# FPGA_ADC1.net
KiCad netlist of a schematic drawn in Altium Designer
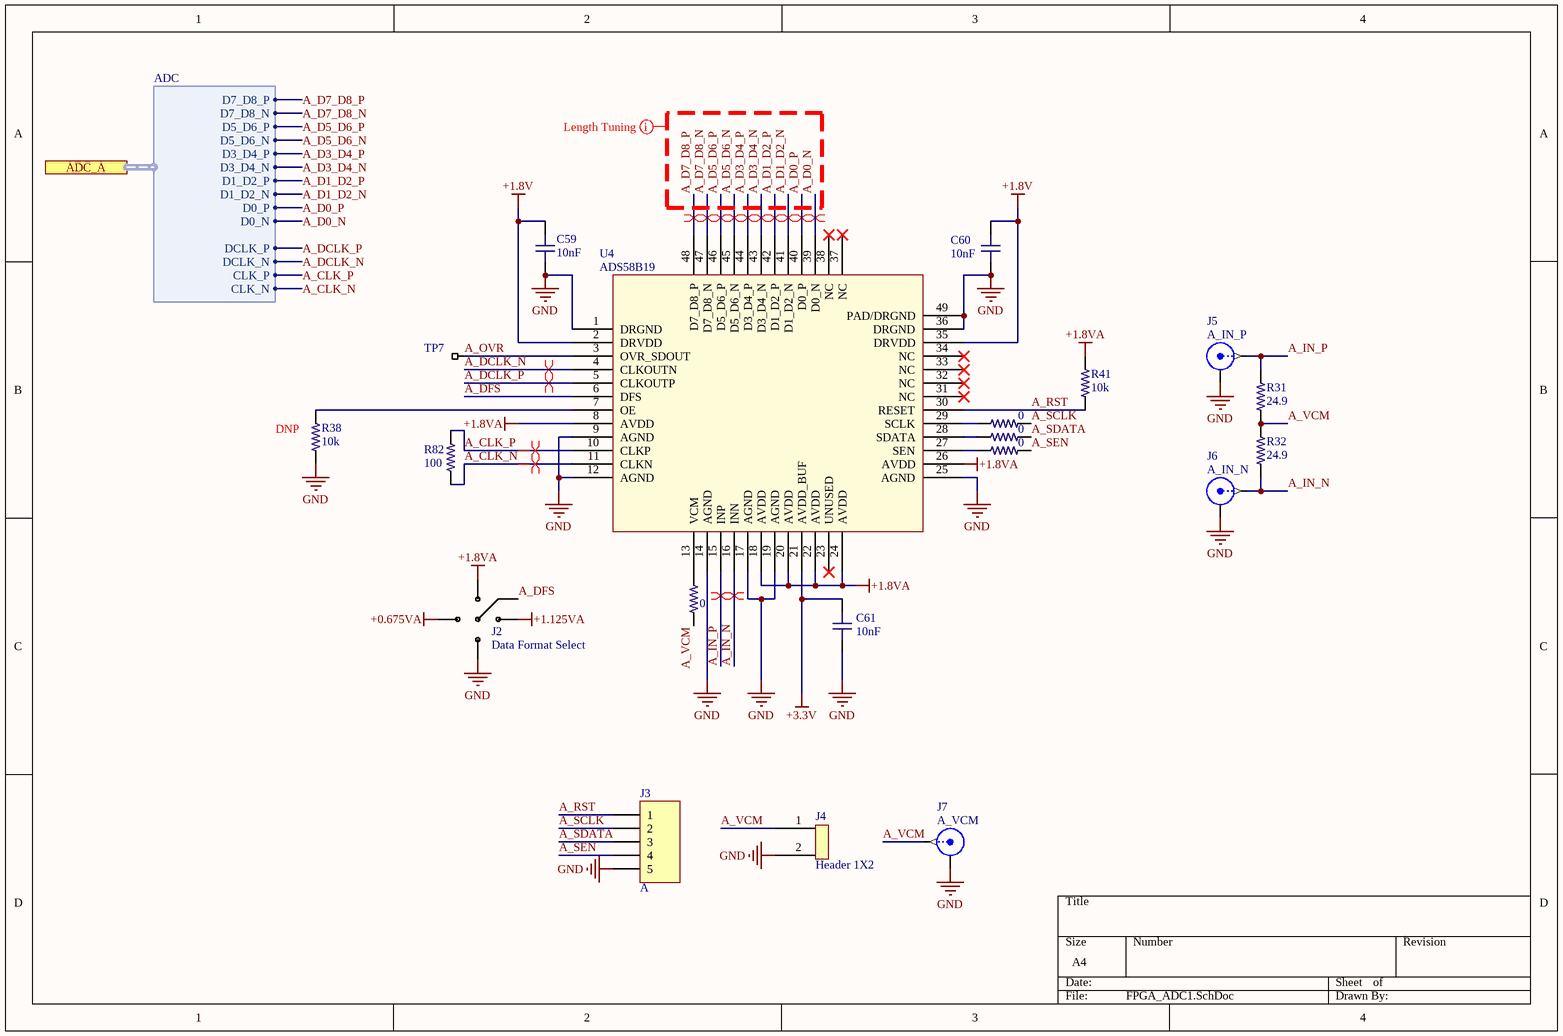
[diagram p0: FPGA_ADC1.SchDoc]

(export (version "E")
  (design (tool "Eeschema 10.0.6"))
  (components
    (comp (ref "C59")
      (value "10nF")
      (footprint "C0603-HIGH-DENSITY")
      (description "CAP CER 10000PF 50V X7R 0603")
      (fields (field (name "Comment") "C0603 10nF 50V X7R"))
      (libsource (lib "Capacitors") (part "C0603 10nF 50V X7R"))
    )
    (comp (ref "C60")
      (value "10nF")
      (footprint "C0603-HIGH-DENSITY")
      (description "CAP CER 10000PF 50V X7R 0603")
      (fields (field (name "Comment") "C0603 10nF 50V X7R"))
      (libsource (lib "Capacitors") (part "C0603 10nF 50V X7R"))
    )
    (comp (ref "C61")
      (value "10nF")
      (footprint "C0603-HIGH-DENSITY")
      (description "CAP CER 10000PF 50V X7R 0603")
      (fields (field (name "Comment") "C0603 10nF 50V X7R"))
      (libsource (lib "Capacitors") (part "C0603 10nF 50V X7R"))
    )
    (comp (ref "J2")
      (value "Data Format Select")
      (footprint "4P Jumper")
      (description "0603 4 Way Solder Jumper")
      (libsource (lib "Switches") (part "4P Jumper"))
    )
    (comp (ref "J3")
      (value "A")
      (footprint "HDR1X5")
      (description "Header, 5-Pin")
      (fields (field (name "PUBLISHER") "Altium Limited"))
      (libsource (lib "Miscellaneous Connectors") (part "Header 5"))
    )
    (comp (ref "J4")
      (value "Header 1X2")
      (footprint "Header 1x2 TH Pitch 2.54mm")
      (libsource (lib "Connectors") (part "Header 1X2"))
    )
    (comp (ref "J5")
      (value "A_IN_P")
      (footprint "SMA Edge Launch (Horizontal)")
      (description "SMA Connector")
      (libsource (lib "Connectors") (part "SMA"))
    )
    (comp (ref "J6")
      (value "A_IN_N")
      (footprint "SMA Edge Launch (Horizontal)")
      (description "SMA Connector")
      (libsource (lib "Connectors") (part "SMA"))
    )
    (comp (ref "J7")
      (value "A_VCM")
      (footprint "SMA_CONN")
      (description "SMA Connector")
      (libsource (lib "") (part "SMA_1"))
    )
    (comp (ref "R31")
      (value "24.9")
      (footprint "R0603-HIGH-DENSITY")
      (description "Chip Resistor, 0603, 24.9 ohms, 0.1W")
      (fields (field (name "Comment") "RC0603FR-0724R9L"))
      (libsource (lib "Resistors") (part "R0603 24.9R 1%"))
    )
    (comp (ref "R32")
      (value "24.9")
      (footprint "R0603-HIGH-DENSITY")
      (description "Chip Resistor, 0603, 24.9 ohms, 0.1W")
      (fields (field (name "Comment") "RC0603FR-0724R9L"))
      (libsource (lib "Resistors") (part "R0603 24.9R 1%"))
    )
    (comp (ref "R36")
      (value "0")
      (footprint "R0603-IPC")
      (description "RES SMD 0 OHM JUMPER 1/10W 0603")
      (fields (field (name "Comment") "R0603 0"))
      (libsource (lib "Resistors") (part "R0603 0"))
    )
    (comp (ref "R37")
      (value "0")
      (footprint "R0603-IPC")
      (description "RES SMD 0 OHM JUMPER 1/10W 0603")
      (fields (field (name "Comment") "R0603 0"))
      (libsource (lib "Resistors") (part "R0603 0"))
    )
    (comp (ref "R38")
      (value "10k")
      (footprint "R0603-IPC-10K")
      (description "RES SMD 10K OHM 1% 1/10W 0603")
      (fields (field (name "Comment") "R0603 10K 1%"))
      (libsource (lib "Resistors") (part "R0603 10K 1%"))
    )
    (comp (ref "R39")
      (value "0")
      (footprint "R0603-IPC")
      (description "RES SMD 0 OHM JUMPER 1/10W 0603")
      (fields (field (name "Comment") "R0603 0"))
      (libsource (lib "Resistors") (part "R0603 0"))
    )
    (comp (ref "R40")
      (value "0")
      (footprint "R0603-IPC")
      (description "RES SMD 0 OHM JUMPER 1/10W 0603")
      (fields (field (name "Comment") "R0603 0"))
      (libsource (lib "Resistors") (part "R0603 0"))
    )
    (comp (ref "R41")
      (value "10k")
      (footprint "R0603-IPC-10K")
      (description "RES SMD 10K OHM 1% 1/10W 0603")
      (fields (field (name "Comment") "R0603 10K 1%"))
      (libsource (lib "Resistors") (part "R0603 10K 1%"))
    )
    (comp (ref "R82")
      (value "100")
      (footprint "R0402-HIGH-DENSITY")
      (description "Chip Resistor, 0402, 100 ohms, 1%, 1/16 W")
      (fields (field (name "Comment") "R0402 100R 1%"))
      (libsource (lib "Resistors") (part "R0402 100R 1%"))
    )
    (comp (ref "TP7")
      (value "Testpoint_SMT")
      (footprint "TESTPOINT_SMT")
      (description "SMT Test Point")
      (libsource (lib "Virtual Parts") (part "Testpoint_SMT"))
    )
    (comp (ref "U4")
      (value "ADS58B19")
      (footprint "VQFN48")
      (description "Single ADC Pipelined 250Msps 9-bit Parallel/LVDS 48-Pin VQFN")
      (libsource (lib "Integrated Circuits") (part "ADS58B19"))
    )
  )
  (nets
    (net (code "2") (name "+0.675VA") (class "Default")
      (node (ref "J2") (pin "4") (pinfunction "4_4") (pintype "passive"))
    )
    (net (code "3") (name "+1.8V") (class "Default")
      (node (ref "C59") (pin "1") (pintype "passive"))
      (node (ref "C60") (pin "1") (pintype "passive"))
      (node (ref "U4") (pin "2") (pinfunction "DRVDD_2") (pintype "passive"))
      (node (ref "U4") (pin "35") (pinfunction "DRVDD_35") (pintype "passive"))
    )
    (net (code "4") (name "+1.8VA") (class "Default")
      (node (ref "J2") (pin "1") (pinfunction "1_1") (pintype "passive"))
      (node (ref "R41") (pin "2") (pintype "passive"))
      (node (ref "U4") (pin "18") (pinfunction "AVDD_18") (pintype "passive"))
      (node (ref "U4") (pin "20") (pinfunction "AVDD_20") (pintype "passive"))
      (node (ref "U4") (pin "22") (pinfunction "AVDD_22") (pintype "passive"))
      (node (ref "U4") (pin "24") (pinfunction "AVDD_24") (pintype "passive"))
      (node (ref "U4") (pin "26") (pinfunction "AVDD_26") (pintype "passive"))
      (node (ref "U4") (pin "8") (pinfunction "AVDD_8") (pintype "passive"))
    )
    (net (code "5") (name "+1.125VA") (class "Default")
      (node (ref "J2") (pin "2") (pinfunction "2_2") (pintype "passive"))
    )
    (net (code "6") (name "+3.3V") (class "Default")
      (node (ref "C61") (pin "1") (pintype "passive"))
      (node (ref "U4") (pin "21") (pinfunction "AVDD_BUF_21") (pintype "passive"))
    )
    (net (code "7") (name "/A_CLK_N") (class "Default")
      (node (ref "R82") (pin "1") (pintype "passive"))
      (node (ref "U4") (pin "11") (pinfunction "CLKN_11") (pintype "passive"))
    )
    (net (code "8") (name "/A_CLK_P") (class "Default")
      (node (ref "R82") (pin "2") (pintype "passive"))
      (node (ref "U4") (pin "10") (pinfunction "CLKP_10") (pintype "passive"))
    )
    (net (code "9") (name "/A_D0_N") (class "Default")
      (node (ref "U4") (pin "39") (pinfunction "D0_N_39") (pintype "passive"))
    )
    (net (code "10") (name "/A_D0_P") (class "Default")
      (node (ref "U4") (pin "40") (pinfunction "D0_P_40") (pintype "passive"))
    )
    (net (code "11") (name "/A_D1_D2_N") (class "Default")
      (node (ref "U4") (pin "41") (pinfunction "D1_D2_N_41") (pintype "passive"))
    )
    (net (code "12") (name "/A_D1_D2_P") (class "Default")
      (node (ref "U4") (pin "42") (pinfunction "D1_D2_P_42") (pintype "passive"))
    )
    (net (code "13") (name "/A_D3_D4_N") (class "Default")
      (node (ref "U4") (pin "43") (pinfunction "D3_D4_N_43") (pintype "passive"))
    )
    (net (code "14") (name "/A_D3_D4_P") (class "Default")
      (node (ref "U4") (pin "44") (pinfunction "D3_D4_P_44") (pintype "passive"))
    )
    (net (code "15") (name "/A_D5_D6_N") (class "Default")
      (node (ref "U4") (pin "45") (pinfunction "D5_D6_N_45") (pintype "passive"))
    )
    (net (code "16") (name "/A_D5_D6_P") (class "Default")
      (node (ref "U4") (pin "46") (pinfunction "D5_D6_P_46") (pintype "passive"))
    )
    (net (code "17") (name "/A_D7_D8_N") (class "Default")
      (node (ref "U4") (pin "47") (pinfunction "D7_D8_N_47") (pintype "passive"))
    )
    (net (code "18") (name "/A_D7_D8_P") (class "Default")
      (node (ref "U4") (pin "48") (pinfunction "D7_D8_P_48") (pintype "passive"))
    )
    (net (code "19") (name "/A_DCLK_N") (class "Default")
      (node (ref "U4") (pin "4") (pinfunction "CLKOUTN_4") (pintype "passive"))
    )
    (net (code "20") (name "/A_DCLK_P") (class "Default")
      (node (ref "U4") (pin "5") (pinfunction "CLKOUTP_5") (pintype "passive"))
    )
    (net (code "21") (name "/A_DFS") (class "Default")
      (node (ref "J2") (pin "5") (pinfunction "5_5") (pintype "passive"))
      (node (ref "U4") (pin "6") (pinfunction "DFS_6") (pintype "passive"))
    )
    (net (code "22") (name "/A_IN_N") (class "Default")
      (node (ref "J6") (pin "1") (pinfunction "X_1") (pintype "output"))
      (node (ref "R32") (pin "1") (pintype "passive"))
      (node (ref "U4") (pin "16") (pinfunction "INN_16") (pintype "passive"))
    )
    (net (code "23") (name "/A_IN_P") (class "Default")
      (node (ref "J5") (pin "1") (pinfunction "X_1") (pintype "output"))
      (node (ref "R31") (pin "2") (pintype "passive"))
      (node (ref "U4") (pin "15") (pinfunction "INP_15") (pintype "passive"))
    )
    (net (code "24") (name "/A_OVR") (class "Default")
      (node (ref "TP7") (pin "1") (pinfunction "1_1") (pintype "passive"))
      (node (ref "U4") (pin "3") (pinfunction "OVR_SDOUT_3") (pintype "passive"))
    )
    (net (code "25") (name "/A_RST") (class "Default")
      (node (ref "J3") (pin "1") (pinfunction "1_1") (pintype "passive"))
      (node (ref "R41") (pin "1") (pintype "passive"))
      (node (ref "U4") (pin "30") (pinfunction "RESET_30") (pintype "passive"))
    )
    (net (code "26") (name "/A_SCLK") (class "Default")
      (node (ref "J3") (pin "2") (pinfunction "2_2") (pintype "passive"))
      (node (ref "R36") (pin "2") (pintype "passive"))
    )
    (net (code "27") (name "/A_SDATA") (class "Default")
      (node (ref "J3") (pin "3") (pinfunction "3_3") (pintype "passive"))
      (node (ref "R37") (pin "2") (pintype "passive"))
    )
    (net (code "28") (name "/A_SEN") (class "Default")
      (node (ref "J3") (pin "4") (pinfunction "4_4") (pintype "passive"))
      (node (ref "R39") (pin "2") (pintype "passive"))
    )
    (net (code "29") (name "/A_VCM") (class "Default")
      (node (ref "J4") (pin "1") (pintype "passive"))
      (node (ref "J7") (pin "C") (pinfunction "X_C") (pintype "output"))
      (node (ref "R31") (pin "1") (pintype "passive"))
      (node (ref "R32") (pin "2") (pintype "passive"))
      (node (ref "R40") (pin "2") (pintype "passive"))
    )
    (net (code "31") (name "GND") (class "Default")
      (node (ref "C59") (pin "2") (pintype "passive"))
      (node (ref "C60") (pin "2") (pintype "passive"))
      (node (ref "C61") (pin "2") (pintype "passive"))
      (node (ref "J2") (pin "3") (pinfunction "3_3") (pintype "passive"))
      (node (ref "J3") (pin "5") (pinfunction "5_5") (pintype "passive"))
      (node (ref "J4") (pin "2") (pintype "passive"))
      (node (ref "J5") (pin "2") (pinfunction "Y_2") (pintype "power_in"))
      (node (ref "J6") (pin "2") (pinfunction "Y_2") (pintype "power_in"))
      (node (ref "J7") (pin "G") (pinfunction "Y_G") (pintype "power_in"))
      (node (ref "R38") (pin "1") (pintype "passive"))
      (node (ref "U4") (pin "1") (pinfunction "DRGND_1") (pintype "passive"))
      (node (ref "U4") (pin "12") (pinfunction "AGND_12") (pintype "passive"))
      (node (ref "U4") (pin "14") (pinfunction "AGND_14") (pintype "passive"))
      (node (ref "U4") (pin "17") (pinfunction "AGND_17") (pintype "passive"))
      (node (ref "U4") (pin "19") (pinfunction "AGND_19") (pintype "passive"))
      (node (ref "U4") (pin "25") (pinfunction "AGND_25") (pintype "passive"))
      (node (ref "U4") (pin "36") (pinfunction "DRGND_36") (pintype "passive"))
      (node (ref "U4") (pin "49") (pinfunction "PAD/DRGND_49") (pintype "passive"))
      (node (ref "U4") (pin "9") (pinfunction "AGND_9") (pintype "passive"))
    )
    (net (code "32") (name "Net-(U4-OE)") (class "Default")
      (node (ref "R38") (pin "2") (pintype "passive"))
      (node (ref "U4") (pin "7") (pinfunction "OE_7") (pintype "passive"))
    )
    (net (code "33") (name "Net-(U4-SCLK)") (class "Default")
      (node (ref "R36") (pin "1") (pintype "passive"))
      (node (ref "U4") (pin "29") (pinfunction "SCLK_29") (pintype "passive"))
    )
    (net (code "34") (name "Net-(U4-SDATA)") (class "Default")
      (node (ref "R37") (pin "1") (pintype "passive"))
      (node (ref "U4") (pin "28") (pinfunction "SDATA_28") (pintype "passive"))
    )
    (net (code "35") (name "Net-(U4-SEN)") (class "Default")
      (node (ref "R39") (pin "1") (pintype "passive"))
      (node (ref "U4") (pin "27") (pinfunction "SEN_27") (pintype "passive"))
    )
    (net (code "36") (name "Net-(U4-VCM)") (class "Default")
      (node (ref "R40") (pin "1") (pintype "passive"))
      (node (ref "U4") (pin "13") (pinfunction "VCM_13") (pintype "passive"))
    )
    (net (code "37") (name "unconnected-(U4-NC-Pad31)") (class "Default")
      (node (ref "U4") (pin "31") (pinfunction "NC_31") (pintype "passive+no_connect"))
    )
    (net (code "38") (name "unconnected-(U4-NC-Pad32)") (class "Default")
      (node (ref "U4") (pin "32") (pinfunction "NC_32") (pintype "passive+no_connect"))
    )
    (net (code "39") (name "unconnected-(U4-NC-Pad33)") (class "Default")
      (node (ref "U4") (pin "33") (pinfunction "NC_33") (pintype "passive+no_connect"))
    )
    (net (code "40") (name "unconnected-(U4-NC-Pad34)") (class "Default")
      (node (ref "U4") (pin "34") (pinfunction "NC_34") (pintype "passive+no_connect"))
    )
    (net (code "41") (name "unconnected-(U4-NC-Pad37)") (class "Default")
      (node (ref "U4") (pin "37") (pinfunction "NC_37") (pintype "passive+no_connect"))
    )
    (net (code "42") (name "unconnected-(U4-NC-Pad38)") (class "Default")
      (node (ref "U4") (pin "38") (pinfunction "NC_38") (pintype "passive+no_connect"))
    )
    (net (code "43") (name "unconnected-(U4-UNUSED-Pad23)") (class "Default")
      (node (ref "U4") (pin "23") (pinfunction "UNUSED_23") (pintype "passive+no_connect"))
    )
  )
)
